# llrf_afe_usb_ftdi.net
KiCad netlist of a schematic drawn in Altium Designer
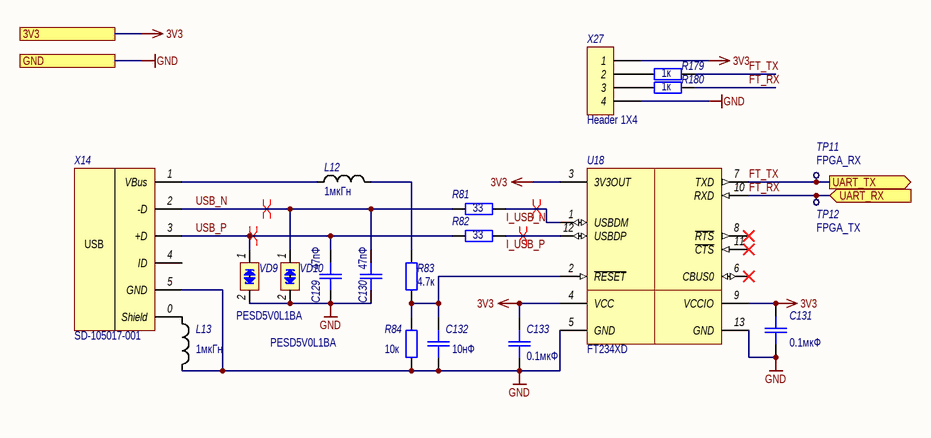
[diagram p0: llrf_afe_usb_ftdi.SchDoc]

(export (version "E")
  (design (tool "Eeschema 10.0.6"))
  (components
    (comp (ref "C129")
      (value "47пФ")
      (footprint "SMD_C0402")
      (description "Capacitor")
      (libsource (lib "Passive") (part "Capacitor"))
    )
    (comp (ref "C130")
      (value "47пФ")
      (footprint "SMD_C0402")
      (description "Capacitor")
      (libsource (lib "Passive") (part "Capacitor"))
    )
    (comp (ref "C131")
      (value "0.1мкФ")
      (footprint "SMD_C0402")
      (description "Capacitor")
      (libsource (lib "Passive") (part "Capacitor"))
    )
    (comp (ref "C132")
      (value "10нФ")
      (footprint "SMD_C0402")
      (description "Capacitor")
      (libsource (lib "Passive") (part "Capacitor"))
    )
    (comp (ref "C133")
      (value "0.1мкФ")
      (footprint "SMD_C0402")
      (description "Capacitor")
      (libsource (lib "Passive") (part "Capacitor"))
    )
    (comp (ref "L12")
      (value "1мкГн")
      (footprint "SMD_0805")
      (description "Inductor")
      (libsource (lib "Passive") (part "Inductor"))
    )
    (comp (ref "L13")
      (value "1мкГн")
      (footprint "SMD_0805")
      (description "Inductor")
      (libsource (lib "Passive") (part "Inductor"))
    )
    (comp (ref "R81")
      (value "33")
      (footprint "SMD_0603")
      (description "PE1206DRM470R01L")
      (libsource (lib "Passive") (part "Resistor"))
    )
    (comp (ref "R82")
      (value "33")
      (footprint "SMD_0603")
      (description "PE1206DRM470R01L")
      (libsource (lib "Passive") (part "Resistor"))
    )
    (comp (ref "R83")
      (value "4.7к")
      (footprint "SMD_0603")
      (description "PE1206DRM470R01L")
      (libsource (lib "") (part "Resistor_1"))
    )
    (comp (ref "R84")
      (value "10к")
      (footprint "SMD_0603")
      (description "PE1206DRM470R01L")
      (libsource (lib "") (part "Resistor_2"))
    )
    (comp (ref "R179")
      (value "1к")
      (footprint "SMD_0603")
      (description "PE1206DRM470R01L")
      (libsource (lib "Passive") (part "Resistor"))
    )
    (comp (ref "R180")
      (value "1к")
      (footprint "SMD_0603")
      (description "PE1206DRM470R01L")
      (libsource (lib "Passive") (part "Resistor"))
    )
    (comp (ref "TP11")
      (value "FPGA_RX")
      (footprint "TestPoint")
      (fields (field (name "TP_NAME") "FPGA_RX"))
      (libsource (lib "Connector") (part "TP"))
    )
    (comp (ref "TP12")
      (value "FPGA_TX")
      (footprint "TestPoint")
      (fields (field (name "TP_NAME") "FPGA_TX"))
      (libsource (lib "Connector") (part "TP"))
    )
    (comp (ref "U18")
      (value "FT234XD")
      (footprint "DFN-12")
      (description "USB TO BASIC UART IC")
      (fields (field (name "НАИМЕНОВАНИЕ") "FT234XD"))
      (libsource (lib "USB") (part "FT234XD"))
    )
    (comp (ref "VD9")
      (value "PESD5V0")
      (footprint "SOD-323")
      (description "Low capacitance bidirectional ESD protection diodes")
      (fields (field (name "НАИМЕНОВАНИЕ") "PESD5V0L1BA"))
      (libsource (lib "Diod") (part "PESDxL1BA"))
    )
    (comp (ref "VD10")
      (value "PESD5V0")
      (footprint "SOD-323")
      (description "Low capacitance bidirectional ESD protection diodes")
      (fields (field (name "НАИМЕНОВАНИЕ") "PESD5V0L1BA"))
      (libsource (lib "Diod") (part "PESDxL1BA"))
    )
    (comp (ref "X14")
      (value "mico-BF")
      (footprint "MicroUSB-Molex-105017")
      (description "MicroUSB bottom mount receptacle, B-type")
      (fields (field (name "НАИМЕНОВАНИЕ") "SD-105017-001"))
      (libsource (lib "Connector") (part "MicroUSB"))
    )
    (comp (ref "X27")
      (value "Header 1X4")
      (footprint "PLS-4")
      (description "Header, 4-Pin, Single row")
      (fields (field (name "НАИМЕНОВАНИЕ") "Header 1X4"))
      (libsource (lib "Connector") (part "Header 1X4"))
    )
  )
  (nets
    (net (code "1") (name "/FT_RX") (class "Default")
      (node (ref "R180") (pin "1") (pinfunction "1_1") (pintype "passive"))
      (node (ref "TP12") (pin "0") (pinfunction "TP_0") (pintype "passive"))
      (node (ref "U18") (pin "10") (pinfunction "RXD_10") (pintype "input"))
    )
    (net (code "2") (name "/FT_TX") (class "Default")
      (node (ref "R179") (pin "1") (pinfunction "1_1") (pintype "passive"))
      (node (ref "TP11") (pin "0") (pinfunction "TP_0") (pintype "passive"))
      (node (ref "U18") (pin "7") (pinfunction "TXD_7") (pintype "output"))
    )
    (net (code "3") (name "/I_USB_N") (class "Default")
      (node (ref "R81") (pin "1") (pinfunction "1_1") (pintype "passive"))
      (node (ref "U18") (pin "1") (pinfunction "USBDM_1") (pintype "bidirectional"))
    )
    (net (code "4") (name "/I_USB_P") (class "Default")
      (node (ref "R82") (pin "1") (pinfunction "1_1") (pintype "passive"))
      (node (ref "U18") (pin "12") (pinfunction "USBDP_12") (pintype "bidirectional"))
    )
    (net (code "5") (name "/USB_N") (class "Default")
      (node (ref "C130") (pin "2") (pinfunction "2_2") (pintype "passive"))
      (node (ref "R81") (pin "2") (pinfunction "2_2") (pintype "passive"))
      (node (ref "VD10") (pin "1") (pinfunction "cathode_1_1") (pintype "passive"))
      (node (ref "X14") (pin "2") (pinfunction "-D_2") (pintype "passive"))
    )
    (net (code "6") (name "/USB_P") (class "Default")
      (node (ref "C129") (pin "2") (pinfunction "2_2") (pintype "passive"))
      (node (ref "R82") (pin "2") (pinfunction "2_2") (pintype "passive"))
      (node (ref "VD9") (pin "1") (pinfunction "cathode_1_1") (pintype "passive"))
      (node (ref "X14") (pin "3") (pinfunction "+D_3") (pintype "passive"))
    )
    (net (code "7") (name "3V3") (class "Default")
      (node (ref "C131") (pin "2") (pinfunction "2_2") (pintype "passive"))
      (node (ref "C133") (pin "2") (pinfunction "2_2") (pintype "passive"))
      (node (ref "U18") (pin "3") (pinfunction "3V3OUT_3") (pintype "power_in"))
      (node (ref "U18") (pin "4") (pinfunction "VCC_4") (pintype "power_in"))
      (node (ref "U18") (pin "9") (pinfunction "VCCIO_9") (pintype "power_in"))
      (node (ref "X27") (pin "1") (pinfunction "1_1") (pintype "passive"))
    )
    (net (code "8") (name "GND") (class "Default")
      (node (ref "C129") (pin "1") (pinfunction "1_1") (pintype "passive"))
      (node (ref "C130") (pin "1") (pinfunction "1_1") (pintype "passive"))
      (node (ref "C131") (pin "1") (pinfunction "1_1") (pintype "passive"))
      (node (ref "C132") (pin "1") (pinfunction "1_1") (pintype "passive"))
      (node (ref "C133") (pin "1") (pinfunction "1_1") (pintype "passive"))
      (node (ref "L13") (pin "2") (pinfunction "2_2") (pintype "passive"))
      (node (ref "R84") (pin "1") (pinfunction "1_1") (pintype "passive"))
      (node (ref "U18") (pin "13") (pinfunction "GND_13") (pintype "power_in"))
      (node (ref "U18") (pin "5") (pinfunction "GND_5") (pintype "power_in"))
      (node (ref "VD10") (pin "2") (pinfunction "cathode_2_2") (pintype "passive"))
      (node (ref "VD9") (pin "2") (pinfunction "cathode_2_2") (pintype "passive"))
      (node (ref "X14") (pin "5") (pinfunction "GND_5") (pintype "passive"))
      (node (ref "X27") (pin "4") (pinfunction "4_4") (pintype "passive"))
    )
    (net (code "9") (name "Net-(L12-Pad2)") (class "Default")
      (node (ref "L12") (pin "2") (pinfunction "2_2") (pintype "passive"))
      (node (ref "R83") (pin "1") (pinfunction "1_1") (pintype "passive"))
    )
    (net (code "10") (name "Net-(R179-Pad2)") (class "Default")
      (node (ref "R179") (pin "2") (pinfunction "2_2") (pintype "passive"))
      (node (ref "X27") (pin "2") (pinfunction "2_2") (pintype "passive"))
    )
    (net (code "11") (name "Net-(R180-Pad2)") (class "Default")
      (node (ref "R180") (pin "2") (pinfunction "2_2") (pintype "passive"))
      (node (ref "X27") (pin "3") (pinfunction "3_3") (pintype "passive"))
    )
    (net (code "12") (name "Net-(U18-~{RESET})") (class "Default")
      (node (ref "C132") (pin "2") (pinfunction "2_2") (pintype "passive"))
      (node (ref "R83") (pin "2") (pinfunction "2_2") (pintype "passive"))
      (node (ref "R84") (pin "2") (pinfunction "2_2") (pintype "passive"))
      (node (ref "U18") (pin "2") (pinfunction "~{RESET}_2") (pintype "input"))
    )
    (net (code "13") (name "Net-(X14-Shield)") (class "Default")
      (node (ref "L13") (pin "1") (pinfunction "1_1") (pintype "passive"))
      (node (ref "X14") (pin "0") (pinfunction "Shield_0") (pintype "passive"))
    )
    (net (code "14") (name "Net-(X14-VBus)") (class "Default")
      (node (ref "L12") (pin "1") (pinfunction "1_1") (pintype "passive"))
      (node (ref "X14") (pin "1") (pinfunction "VBus_1") (pintype "passive"))
    )
    (net (code "15") (name "unconnected-(U18-CBUS0-Pad6)") (class "Default")
      (node (ref "U18") (pin "6") (pinfunction "CBUS0_6") (pintype "bidirectional+no_connect"))
    )
    (net (code "16") (name "unconnected-(U18-~{CTS}-Pad11)") (class "Default")
      (node (ref "U18") (pin "11") (pinfunction "~{CTS}_11") (pintype "input+no_connect"))
    )
    (net (code "17") (name "unconnected-(U18-~{RTS}-Pad8)") (class "Default")
      (node (ref "U18") (pin "8") (pinfunction "~{RTS}_8") (pintype "output+no_connect"))
    )
    (net (code "18") (name "unconnected-(X14-ID-Pad4)") (class "Default")
      (node (ref "X14") (pin "4") (pinfunction "ID_4") (pintype "passive"))
    )
  )
)
